# bms_board.net
KiCad netlist of a schematic drawn in EAGLE
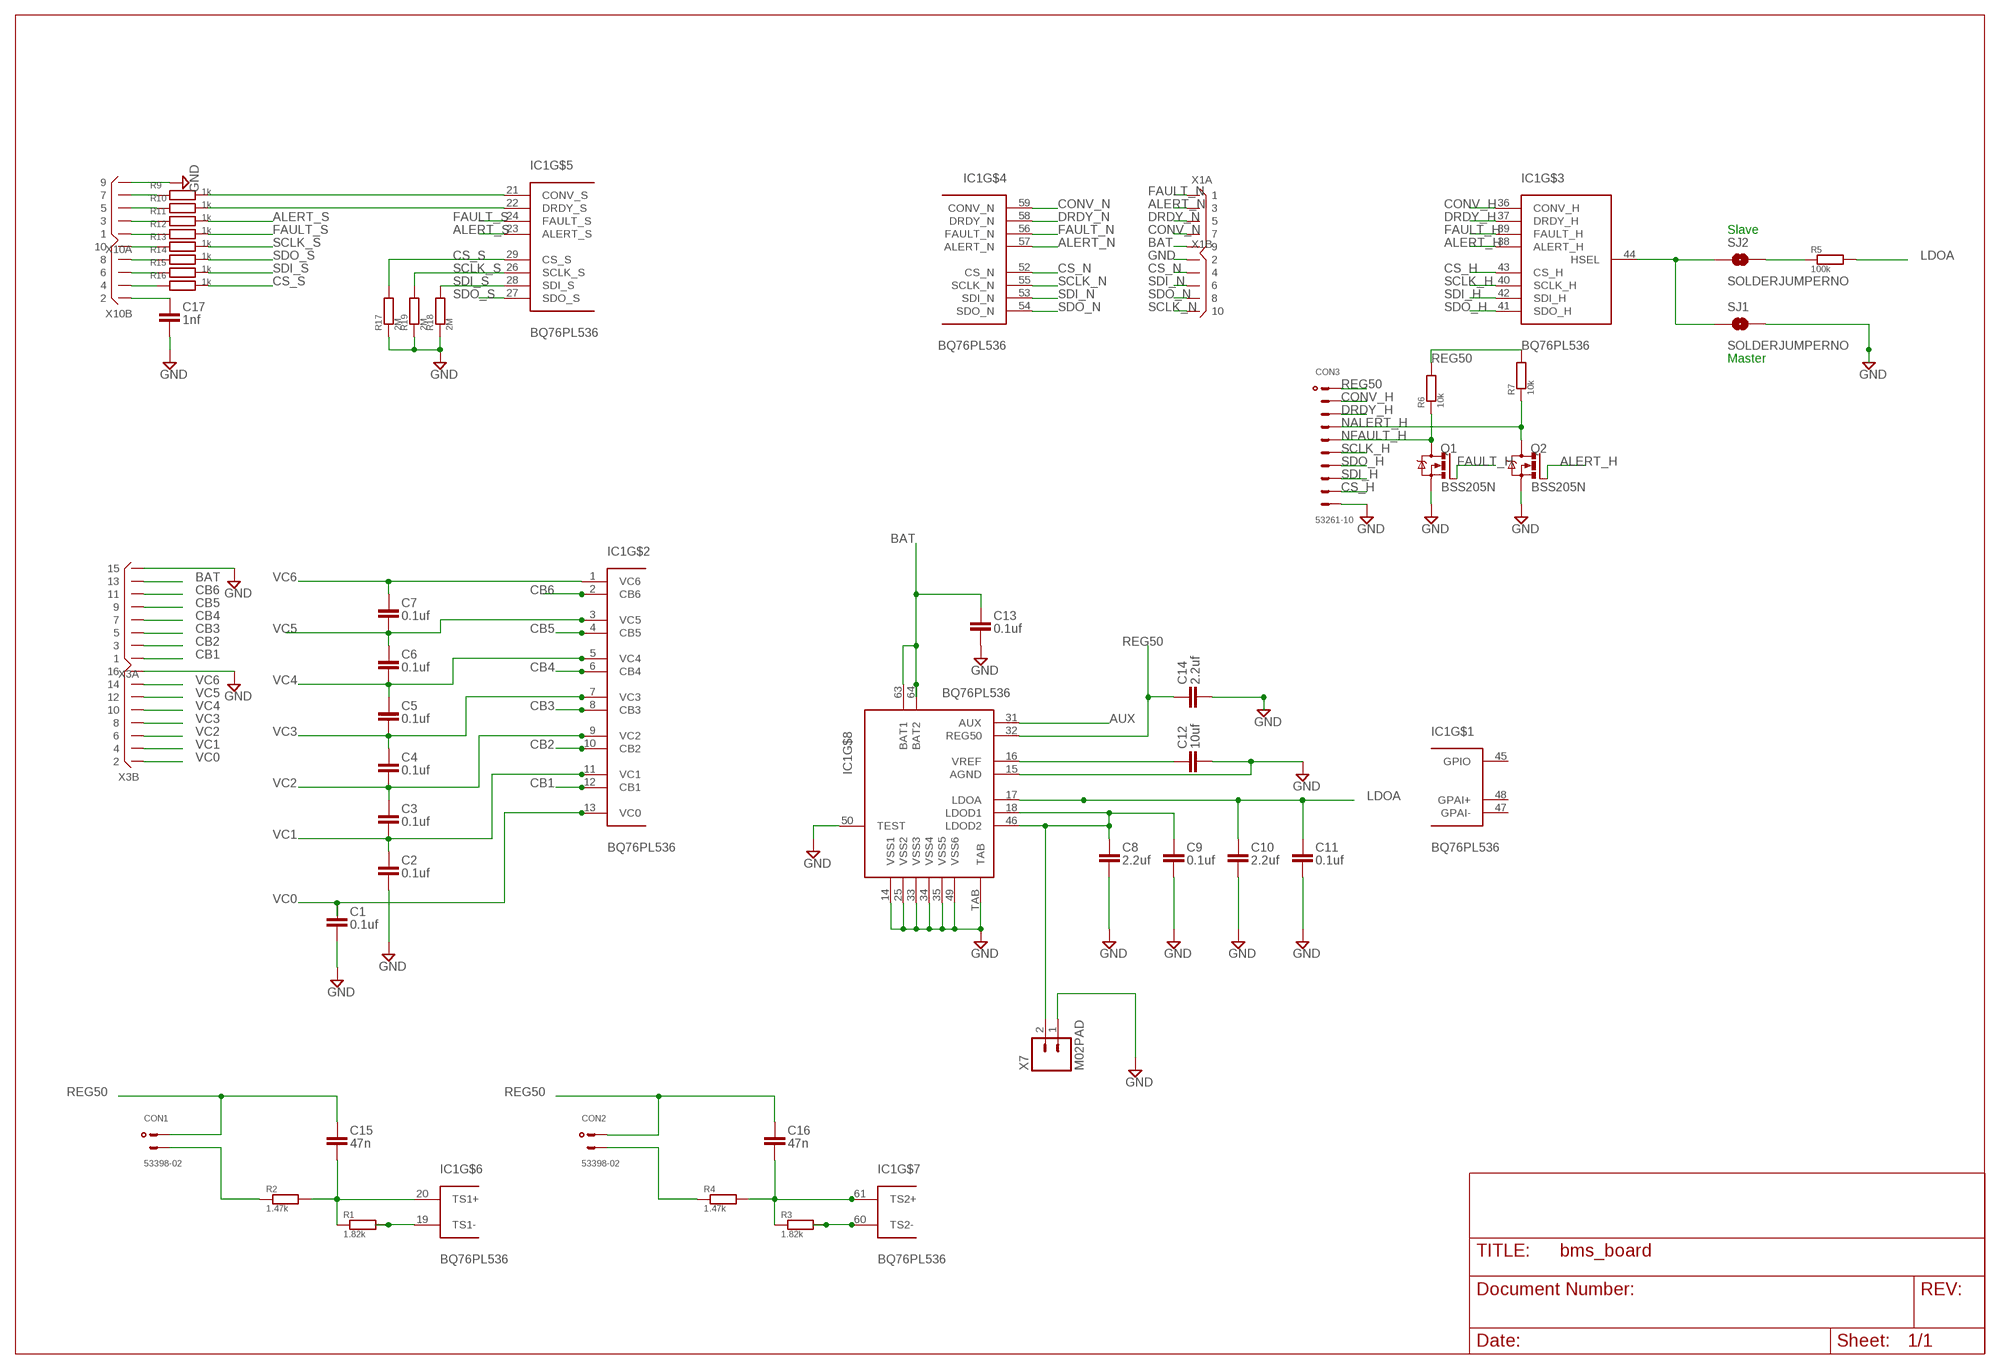
[diagram p0: schematic, sheet 1]

(export (version "E")
  (design (tool "Eeschema 10.0.6"))
  (components
    (comp (ref "C1")
      (value "0.1uf")
      (footprint "eagle-import:C0805")
      (libsource (lib "eagle-import") (part "CSTD"))
    )
    (comp (ref "C2")
      (value "0.1uf")
      (footprint "eagle-import:C0805")
      (libsource (lib "eagle-import") (part "CSTD"))
    )
    (comp (ref "C3")
      (value "0.1uf")
      (footprint "eagle-import:C0805")
      (libsource (lib "eagle-import") (part "CSTD"))
    )
    (comp (ref "C4")
      (value "0.1uf")
      (footprint "eagle-import:C0805")
      (libsource (lib "eagle-import") (part "CSTD"))
    )
    (comp (ref "C5")
      (value "0.1uf")
      (footprint "eagle-import:C0805")
      (libsource (lib "eagle-import") (part "CSTD"))
    )
    (comp (ref "C6")
      (value "0.1uf")
      (footprint "eagle-import:C0805")
      (libsource (lib "eagle-import") (part "CSTD"))
    )
    (comp (ref "C7")
      (value "0.1uf")
      (footprint "eagle-import:C0805")
      (libsource (lib "eagle-import") (part "CSTD"))
    )
    (comp (ref "C8")
      (value "2.2uf")
      (footprint "eagle-import:C0805")
      (libsource (lib "eagle-import") (part "CSTD"))
    )
    (comp (ref "C9")
      (value "0.1uf")
      (footprint "eagle-import:C0805")
      (libsource (lib "eagle-import") (part "CSTD"))
    )
    (comp (ref "C10")
      (value "2.2uf")
      (footprint "eagle-import:C0805")
      (libsource (lib "eagle-import") (part "CSTD"))
    )
    (comp (ref "C11")
      (value "0.1uf")
      (footprint "eagle-import:C0805")
      (libsource (lib "eagle-import") (part "CSTD"))
    )
    (comp (ref "C12")
      (value "10uf")
      (footprint "eagle-import:C0805")
      (libsource (lib "eagle-import") (part "CSTD"))
    )
    (comp (ref "C13")
      (value "0.1uf")
      (footprint "eagle-import:C0805")
      (libsource (lib "eagle-import") (part "CSTD"))
    )
    (comp (ref "C14")
      (value "2.2uf")
      (footprint "eagle-import:C0805")
      (libsource (lib "eagle-import") (part "CSTD"))
    )
    (comp (ref "C15")
      (value "47n")
      (footprint "eagle-import:C0805")
      (libsource (lib "eagle-import") (part "CSTD"))
    )
    (comp (ref "C16")
      (value "47n")
      (footprint "eagle-import:C0805")
      (libsource (lib "eagle-import") (part "CSTD"))
    )
    (comp (ref "C17")
      (value "1nf")
      (footprint "eagle-import:C0805")
      (libsource (lib "eagle-import") (part "CSTD"))
    )
    (comp (ref "CON1")
      (value "53398-02")
      (footprint "eagle-import:53398-02")
      (libsource (lib "eagle-import") (part "53?-02398"))
    )
    (comp (ref "CON2")
      (value "53398-02")
      (footprint "eagle-import:53398-02")
      (libsource (lib "eagle-import") (part "53?-02398"))
    )
    (comp (ref "CON3")
      (value "53261-10")
      (footprint "eagle-import:53261-10")
      (libsource (lib "eagle-import") (part "53?-10261"))
    )
    (comp (ref "IC1")
      (value "BQ76PL536")
      (footprint "eagle-import:LQFP-64")
      (libsource (lib "eagle-import") (part "BQ76PL536"))
    )
    (comp (ref "Q1")
      (value "BSS205N")
      (footprint "eagle-import:SOT23")
      (libsource (lib "eagle-import") (part "BSS205N"))
    )
    (comp (ref "Q2")
      (value "BSS205N")
      (footprint "eagle-import:SOT23")
      (libsource (lib "eagle-import") (part "BSS205N"))
    )
    (comp (ref "R1")
      (value "1.82k")
      (footprint "eagle-import:R0805")
      (libsource (lib "eagle-import") (part "R"))
    )
    (comp (ref "R2")
      (value "1.47k")
      (footprint "eagle-import:R0805")
      (libsource (lib "eagle-import") (part "R"))
    )
    (comp (ref "R3")
      (value "1.82k")
      (footprint "eagle-import:R0805")
      (libsource (lib "eagle-import") (part "R"))
    )
    (comp (ref "R4")
      (value "1.47k")
      (footprint "eagle-import:R0805")
      (libsource (lib "eagle-import") (part "R"))
    )
    (comp (ref "R5")
      (value "100k")
      (footprint "eagle-import:R0805")
      (libsource (lib "eagle-import") (part "R"))
    )
    (comp (ref "R6")
      (value "10k")
      (footprint "eagle-import:R0805")
      (libsource (lib "eagle-import") (part "R"))
    )
    (comp (ref "R7")
      (value "10k")
      (footprint "eagle-import:R0805")
      (libsource (lib "eagle-import") (part "R"))
    )
    (comp (ref "R9")
      (value "1k")
      (footprint "eagle-import:R0805")
      (libsource (lib "eagle-import") (part "R"))
    )
    (comp (ref "R10")
      (value "1k")
      (footprint "eagle-import:R0805")
      (libsource (lib "eagle-import") (part "R"))
    )
    (comp (ref "R11")
      (value "1k")
      (footprint "eagle-import:R0805")
      (libsource (lib "eagle-import") (part "R"))
    )
    (comp (ref "R12")
      (value "1k")
      (footprint "eagle-import:R0805")
      (libsource (lib "eagle-import") (part "R"))
    )
    (comp (ref "R13")
      (value "1k")
      (footprint "eagle-import:R0805")
      (libsource (lib "eagle-import") (part "R"))
    )
    (comp (ref "R14")
      (value "1k")
      (footprint "eagle-import:R0805")
      (libsource (lib "eagle-import") (part "R"))
    )
    (comp (ref "R15")
      (value "1k")
      (footprint "eagle-import:R0805")
      (libsource (lib "eagle-import") (part "R"))
    )
    (comp (ref "R16")
      (value "1k")
      (footprint "eagle-import:R0805")
      (libsource (lib "eagle-import") (part "R"))
    )
    (comp (ref "R17")
      (value "2M")
      (footprint "eagle-import:R0805")
      (libsource (lib "eagle-import") (part "R"))
    )
    (comp (ref "R18")
      (value "2M")
      (footprint "eagle-import:R0805")
      (libsource (lib "eagle-import") (part "R"))
    )
    (comp (ref "R19")
      (value "2M")
      (footprint "eagle-import:R0805")
      (libsource (lib "eagle-import") (part "R"))
    )
    (comp (ref "SJ1")
      (value "SOLDERJUMPERNO")
      (footprint "eagle-import:SJ_2S-NO")
      (libsource (lib "eagle-import") (part "SOLDERJUMPERNO"))
    )
    (comp (ref "SJ2")
      (value "SOLDERJUMPERNO")
      (footprint "eagle-import:SJ_2S-NO")
      (libsource (lib "eagle-import") (part "SOLDERJUMPERNO"))
    )
    (comp (ref "X1")
      (value "X05X2ICR")
      (footprint "eagle-import:X10ICR")
      (libsource (lib "eagle-import") (part "X05X2ICR"))
    )
    (comp (ref "X3")
      (value "X08X2DR")
      (footprint "eagle-import:X16R-DIL")
      (libsource (lib "eagle-import") (part "X08X2DR"))
    )
    (comp (ref "X7")
      (value "M02PAD")
      (footprint "eagle-import:1X02")
      (libsource (lib "eagle-import") (part "M02PAD"))
    )
    (comp (ref "X10")
      (value "X05X2ICR")
      (footprint "eagle-import:X10ICR")
      (libsource (lib "eagle-import") (part "X05X2ICR"))
    )
  )
  (nets
    (net (code "1") (name "/ALERT_H") (class "Default")
      (node (ref "IC1") (pin "38") (pinfunction "ALERT_H_38") (pintype "bidirectional"))
      (node (ref "Q2") (pin "1") (pinfunction "G_1") (pintype "passive"))
    )
    (net (code "2") (name "/ALERT_N") (class "Default")
      (node (ref "IC1") (pin "57") (pinfunction "ALERT_N_57") (pintype "bidirectional"))
      (node (ref "X1") (pin "3") (pinfunction "3_3") (pintype "bidirectional"))
    )
    (net (code "3") (name "/ALERT_S") (class "Default")
      (node (ref "IC1") (pin "23") (pinfunction "ALERT_S_23") (pintype "bidirectional"))
      (node (ref "R11") (pin "2") (pinfunction "2_2") (pintype "passive"))
    )
    (net (code "4") (name "/AUX") (class "Default")
      (node (ref "IC1") (pin "31") (pinfunction "AUX_31") (pintype "bidirectional"))
    )
    (net (code "5") (name "/BAT") (class "Default")
      (node (ref "C13") (pin "2") (pinfunction "2_2") (pintype "passive"))
      (node (ref "IC1") (pin "63") (pinfunction "BAT1_63") (pintype "bidirectional"))
      (node (ref "IC1") (pin "64") (pinfunction "BAT2_64") (pintype "bidirectional"))
      (node (ref "X1") (pin "9") (pinfunction "9_9") (pintype "bidirectional"))
      (node (ref "X3") (pin "13") (pinfunction "13_13") (pintype "bidirectional"))
    )
    (net (code "6") (name "/CB1") (class "Default")
      (node (ref "IC1") (pin "12") (pinfunction "CB1_12") (pintype "bidirectional"))
      (node (ref "X3") (pin "1") (pinfunction "1_1") (pintype "bidirectional"))
    )
    (net (code "7") (name "/CB2") (class "Default")
      (node (ref "IC1") (pin "10") (pinfunction "CB2_10") (pintype "bidirectional"))
      (node (ref "X3") (pin "3") (pinfunction "3_3") (pintype "bidirectional"))
    )
    (net (code "8") (name "/CB3") (class "Default")
      (node (ref "IC1") (pin "8") (pinfunction "CB3_8") (pintype "bidirectional"))
      (node (ref "X3") (pin "5") (pinfunction "5_5") (pintype "bidirectional"))
    )
    (net (code "9") (name "/CB4") (class "Default")
      (node (ref "IC1") (pin "6") (pinfunction "CB4_6") (pintype "bidirectional"))
      (node (ref "X3") (pin "7") (pinfunction "7_7") (pintype "bidirectional"))
    )
    (net (code "10") (name "/CB5") (class "Default")
      (node (ref "IC1") (pin "4") (pinfunction "CB5_4") (pintype "bidirectional"))
      (node (ref "X3") (pin "9") (pinfunction "9_9") (pintype "bidirectional"))
    )
    (net (code "11") (name "/CB6") (class "Default")
      (node (ref "IC1") (pin "2") (pinfunction "CB6_2") (pintype "bidirectional"))
      (node (ref "X3") (pin "11") (pinfunction "11_11") (pintype "bidirectional"))
    )
    (net (code "12") (name "/CONV_H") (class "Default")
      (node (ref "CON3") (pin "2") (pinfunction "2_2") (pintype "passive"))
      (node (ref "IC1") (pin "36") (pinfunction "CONV_H_36") (pintype "bidirectional"))
    )
    (net (code "13") (name "/CONV_N") (class "Default")
      (node (ref "IC1") (pin "59") (pinfunction "CONV_N_59") (pintype "bidirectional"))
      (node (ref "X1") (pin "7") (pinfunction "7_7") (pintype "bidirectional"))
    )
    (net (code "14") (name "/CS_H") (class "Default")
      (node (ref "CON3") (pin "9") (pinfunction "9_9") (pintype "passive"))
      (node (ref "IC1") (pin "43") (pinfunction "CS_H_43") (pintype "bidirectional"))
    )
    (net (code "15") (name "/CS_N") (class "Default")
      (node (ref "IC1") (pin "52") (pinfunction "CS_N_52") (pintype "bidirectional"))
      (node (ref "X1") (pin "4") (pinfunction "4_4") (pintype "bidirectional"))
    )
    (net (code "16") (name "/CS_S") (class "Default")
      (node (ref "IC1") (pin "29") (pinfunction "CS_S_29") (pintype "bidirectional"))
      (node (ref "R16") (pin "2") (pinfunction "2_2") (pintype "passive"))
      (node (ref "R17") (pin "2") (pinfunction "2_2") (pintype "passive"))
    )
    (net (code "17") (name "/DRDY_H") (class "Default")
      (node (ref "CON3") (pin "3") (pinfunction "3_3") (pintype "passive"))
      (node (ref "IC1") (pin "37") (pinfunction "DRDY_H_37") (pintype "bidirectional"))
    )
    (net (code "18") (name "/DRDY_N") (class "Default")
      (node (ref "IC1") (pin "58") (pinfunction "DRDY_N_58") (pintype "bidirectional"))
      (node (ref "X1") (pin "5") (pinfunction "5_5") (pintype "bidirectional"))
    )
    (net (code "19") (name "/FAULT_H") (class "Default")
      (node (ref "IC1") (pin "39") (pinfunction "FAULT_H_39") (pintype "bidirectional"))
      (node (ref "Q1") (pin "1") (pinfunction "G_1") (pintype "passive"))
    )
    (net (code "20") (name "/FAULT_N") (class "Default")
      (node (ref "IC1") (pin "56") (pinfunction "FAULT_N_56") (pintype "bidirectional"))
      (node (ref "X1") (pin "1") (pinfunction "1_1") (pintype "bidirectional"))
    )
    (net (code "21") (name "/FAULT_S") (class "Default")
      (node (ref "IC1") (pin "24") (pinfunction "FAULT_S_24") (pintype "bidirectional"))
      (node (ref "R12") (pin "2") (pinfunction "2_2") (pintype "passive"))
    )
    (net (code "22") (name "/LDOA") (class "Default")
      (node (ref "C10") (pin "2") (pinfunction "2_2") (pintype "passive"))
      (node (ref "C11") (pin "2") (pinfunction "2_2") (pintype "passive"))
      (node (ref "IC1") (pin "17") (pinfunction "LDOA_17") (pintype "bidirectional"))
      (node (ref "R5") (pin "2") (pinfunction "2_2") (pintype "passive"))
    )
    (net (code "23") (name "/NALERT_H") (class "Default")
      (node (ref "CON3") (pin "4") (pinfunction "4_4") (pintype "passive"))
      (node (ref "Q2") (pin "3") (pinfunction "D_3") (pintype "passive"))
      (node (ref "R7") (pin "1") (pinfunction "1_1") (pintype "passive"))
    )
    (net (code "24") (name "/NFAULT_H") (class "Default")
      (node (ref "CON3") (pin "5") (pinfunction "5_5") (pintype "passive"))
      (node (ref "Q1") (pin "3") (pinfunction "D_3") (pintype "passive"))
      (node (ref "R6") (pin "1") (pinfunction "1_1") (pintype "passive"))
    )
    (net (code "25") (name "/REG50") (class "Default")
      (node (ref "C14") (pin "2") (pinfunction "2_2") (pintype "passive"))
      (node (ref "C15") (pin "2") (pinfunction "2_2") (pintype "passive"))
      (node (ref "C16") (pin "2") (pinfunction "2_2") (pintype "passive"))
      (node (ref "CON1") (pin "1") (pinfunction "1_1") (pintype "passive"))
      (node (ref "CON2") (pin "1") (pinfunction "1_1") (pintype "passive"))
      (node (ref "CON3") (pin "1") (pinfunction "1_1") (pintype "passive"))
      (node (ref "IC1") (pin "32") (pinfunction "REG50_32") (pintype "bidirectional"))
      (node (ref "R6") (pin "2") (pinfunction "2_2") (pintype "passive"))
      (node (ref "R7") (pin "2") (pinfunction "2_2") (pintype "passive"))
    )
    (net (code "26") (name "/SCLK_H") (class "Default")
      (node (ref "CON3") (pin "6") (pinfunction "6_6") (pintype "passive"))
      (node (ref "IC1") (pin "40") (pinfunction "SCLK_H_40") (pintype "bidirectional"))
    )
    (net (code "27") (name "/SCLK_N") (class "Default")
      (node (ref "IC1") (pin "55") (pinfunction "SCLK_N_55") (pintype "bidirectional"))
      (node (ref "X1") (pin "10") (pinfunction "10_10") (pintype "bidirectional"))
    )
    (net (code "28") (name "/SCLK_S") (class "Default")
      (node (ref "IC1") (pin "26") (pinfunction "SCLK_S_26") (pintype "bidirectional"))
      (node (ref "R13") (pin "2") (pinfunction "2_2") (pintype "passive"))
      (node (ref "R19") (pin "2") (pinfunction "2_2") (pintype "passive"))
    )
    (net (code "29") (name "/SDI_H") (class "Default")
      (node (ref "CON3") (pin "8") (pinfunction "8_8") (pintype "passive"))
      (node (ref "IC1") (pin "42") (pinfunction "SDI_H_42") (pintype "bidirectional"))
    )
    (net (code "30") (name "/SDI_N") (class "Default")
      (node (ref "IC1") (pin "53") (pinfunction "SDI_N_53") (pintype "bidirectional"))
      (node (ref "X1") (pin "6") (pinfunction "6_6") (pintype "bidirectional"))
    )
    (net (code "31") (name "/SDI_S") (class "Default")
      (node (ref "IC1") (pin "28") (pinfunction "SDI_S_28") (pintype "bidirectional"))
      (node (ref "R15") (pin "2") (pinfunction "2_2") (pintype "passive"))
      (node (ref "R18") (pin "2") (pinfunction "2_2") (pintype "passive"))
    )
    (net (code "32") (name "/SDO_H") (class "Default")
      (node (ref "CON3") (pin "7") (pinfunction "7_7") (pintype "passive"))
      (node (ref "IC1") (pin "41") (pinfunction "SDO_H_41") (pintype "bidirectional"))
    )
    (net (code "33") (name "/SDO_N") (class "Default")
      (node (ref "IC1") (pin "54") (pinfunction "SDO_N_54") (pintype "bidirectional"))
      (node (ref "X1") (pin "8") (pinfunction "8_8") (pintype "bidirectional"))
    )
    (net (code "34") (name "/SDO_S") (class "Default")
      (node (ref "IC1") (pin "27") (pinfunction "SDO_S_27") (pintype "bidirectional"))
      (node (ref "R14") (pin "2") (pinfunction "2_2") (pintype "passive"))
    )
    (net (code "35") (name "/VC0") (class "Default")
      (node (ref "C1") (pin "2") (pinfunction "2_2") (pintype "passive"))
      (node (ref "IC1") (pin "13") (pinfunction "VC0_13") (pintype "bidirectional"))
      (node (ref "X3") (pin "2") (pinfunction "2_2") (pintype "bidirectional"))
    )
    (net (code "36") (name "/VC1") (class "Default")
      (node (ref "C2") (pin "2") (pinfunction "2_2") (pintype "passive"))
      (node (ref "C3") (pin "1") (pinfunction "1_1") (pintype "passive"))
      (node (ref "IC1") (pin "11") (pinfunction "VC1_11") (pintype "bidirectional"))
      (node (ref "X3") (pin "4") (pinfunction "4_4") (pintype "bidirectional"))
    )
    (net (code "37") (name "/VC2") (class "Default")
      (node (ref "C3") (pin "2") (pinfunction "2_2") (pintype "passive"))
      (node (ref "C4") (pin "1") (pinfunction "1_1") (pintype "passive"))
      (node (ref "IC1") (pin "9") (pinfunction "VC2_9") (pintype "bidirectional"))
      (node (ref "X3") (pin "6") (pinfunction "6_6") (pintype "bidirectional"))
    )
    (net (code "38") (name "/VC3") (class "Default")
      (node (ref "C4") (pin "2") (pinfunction "2_2") (pintype "passive"))
      (node (ref "C5") (pin "1") (pinfunction "1_1") (pintype "passive"))
      (node (ref "IC1") (pin "7") (pinfunction "VC3_7") (pintype "bidirectional"))
      (node (ref "X3") (pin "8") (pinfunction "8_8") (pintype "bidirectional"))
    )
    (net (code "39") (name "/VC4") (class "Default")
      (node (ref "C5") (pin "2") (pinfunction "2_2") (pintype "passive"))
      (node (ref "C6") (pin "1") (pinfunction "1_1") (pintype "passive"))
      (node (ref "IC1") (pin "5") (pinfunction "VC4_5") (pintype "bidirectional"))
      (node (ref "X3") (pin "10") (pinfunction "10_10") (pintype "bidirectional"))
    )
    (net (code "40") (name "/VC5") (class "Default")
      (node (ref "C6") (pin "2") (pinfunction "2_2") (pintype "passive"))
      (node (ref "C7") (pin "1") (pinfunction "1_1") (pintype "passive"))
      (node (ref "IC1") (pin "3") (pinfunction "VC5_3") (pintype "bidirectional"))
      (node (ref "X3") (pin "12") (pinfunction "12_12") (pintype "bidirectional"))
    )
    (net (code "41") (name "/VC6") (class "Default")
      (node (ref "C7") (pin "2") (pinfunction "2_2") (pintype "passive"))
      (node (ref "IC1") (pin "1") (pinfunction "VC6_1") (pintype "bidirectional"))
      (node (ref "X3") (pin "14") (pinfunction "14_14") (pintype "bidirectional"))
    )
    (net (code "42") (name "GND") (class "Default")
      (node (ref "C1") (pin "1") (pinfunction "1_1") (pintype "passive"))
      (node (ref "C10") (pin "1") (pinfunction "1_1") (pintype "passive"))
      (node (ref "C11") (pin "1") (pinfunction "1_1") (pintype "passive"))
      (node (ref "C12") (pin "1") (pinfunction "1_1") (pintype "passive"))
      (node (ref "C13") (pin "1") (pinfunction "1_1") (pintype "passive"))
      (node (ref "C14") (pin "1") (pinfunction "1_1") (pintype "passive"))
      (node (ref "C17") (pin "1") (pinfunction "1_1") (pintype "passive"))
      (node (ref "C2") (pin "1") (pinfunction "1_1") (pintype "passive"))
      (node (ref "C8") (pin "1") (pinfunction "1_1") (pintype "passive"))
      (node (ref "C9") (pin "1") (pinfunction "1_1") (pintype "passive"))
      (node (ref "CON3") (pin "10") (pinfunction "10_10") (pintype "passive"))
      (node (ref "IC1") (pin "14") (pinfunction "VSS1_14") (pintype "bidirectional"))
      (node (ref "IC1") (pin "15") (pinfunction "AGND_15") (pintype "bidirectional"))
      (node (ref "IC1") (pin "25") (pinfunction "VSS2_25") (pintype "bidirectional"))
      (node (ref "IC1") (pin "33") (pinfunction "VSS3_33") (pintype "bidirectional"))
      (node (ref "IC1") (pin "34") (pinfunction "VSS4_34") (pintype "bidirectional"))
      (node (ref "IC1") (pin "35") (pinfunction "VSS5_35") (pintype "bidirectional"))
      (node (ref "IC1") (pin "49") (pinfunction "VSS6_49") (pintype "bidirectional"))
      (node (ref "IC1") (pin "50") (pinfunction "TEST_50") (pintype "bidirectional"))
      (node (ref "IC1") (pin "TAB") (pinfunction "TAB_TAB") (pintype "bidirectional"))
      (node (ref "Q1") (pin "2") (pinfunction "S_2") (pintype "passive"))
      (node (ref "Q2") (pin "2") (pinfunction "S_2") (pintype "passive"))
      (node (ref "R17") (pin "1") (pinfunction "1_1") (pintype "passive"))
      (node (ref "R18") (pin "1") (pinfunction "1_1") (pintype "passive"))
      (node (ref "R19") (pin "1") (pinfunction "1_1") (pintype "passive"))
      (node (ref "SJ1") (pin "2") (pinfunction "2_2") (pintype "passive"))
      (node (ref "X1") (pin "2") (pinfunction "2_2") (pintype "bidirectional"))
      (node (ref "X10") (pin "9") (pinfunction "9_9") (pintype "bidirectional"))
      (node (ref "X3") (pin "15") (pinfunction "15_15") (pintype "bidirectional"))
      (node (ref "X3") (pin "16") (pinfunction "16_16") (pintype "bidirectional"))
      (node (ref "X7") (pin "1") (pinfunction "1_1") (pintype "passive"))
    )
    (net (code "43") (name "Net-(C17-Pad2)") (class "Default")
      (node (ref "C17") (pin "2") (pinfunction "2_2") (pintype "passive"))
      (node (ref "X10") (pin "2") (pinfunction "2_2") (pintype "bidirectional"))
    )
    (net (code "44") (name "Net-(CON1-Pad2)") (class "Default")
      (node (ref "CON1") (pin "2") (pinfunction "2_2") (pintype "passive"))
      (node (ref "R2") (pin "1") (pinfunction "1_1") (pintype "passive"))
    )
    (net (code "45") (name "Net-(CON2-Pad2)") (class "Default")
      (node (ref "CON2") (pin "2") (pinfunction "2_2") (pintype "passive"))
      (node (ref "R4") (pin "1") (pinfunction "1_1") (pintype "passive"))
    )
    (net (code "46") (name "Net-(IC1C-HSEL)") (class "Default")
      (node (ref "IC1") (pin "44") (pinfunction "HSEL_44") (pintype "bidirectional"))
      (node (ref "SJ1") (pin "1") (pinfunction "1_1") (pintype "passive"))
      (node (ref "SJ2") (pin "1") (pinfunction "1_1") (pintype "passive"))
    )
    (net (code "47") (name "Net-(IC1E-CONV_S)") (class "Default")
      (node (ref "IC1") (pin "21") (pinfunction "CONV_S_21") (pintype "bidirectional"))
      (node (ref "R9") (pin "2") (pinfunction "2_2") (pintype "passive"))
    )
    (net (code "48") (name "Net-(IC1E-DRDY_S)") (class "Default")
      (node (ref "IC1") (pin "22") (pinfunction "DRDY_S_22") (pintype "bidirectional"))
      (node (ref "R10") (pin "2") (pinfunction "2_2") (pintype "passive"))
    )
    (net (code "49") (name "Net-(IC1F-TS1+)") (class "Default")
      (node (ref "C15") (pin "1") (pinfunction "1_1") (pintype "passive"))
      (node (ref "IC1") (pin "20") (pinfunction "TS1+_20") (pintype "bidirectional"))
      (node (ref "R1") (pin "1") (pinfunction "1_1") (pintype "passive"))
      (node (ref "R2") (pin "2") (pinfunction "2_2") (pintype "passive"))
    )
    (net (code "50") (name "Net-(IC1F-TS1-)") (class "Default")
      (node (ref "IC1") (pin "19") (pinfunction "TS1-_19") (pintype "bidirectional"))
      (node (ref "R1") (pin "2") (pinfunction "2_2") (pintype "passive"))
    )
    (net (code "51") (name "Net-(IC1G-TS2+)") (class "Default")
      (node (ref "C16") (pin "1") (pinfunction "1_1") (pintype "passive"))
      (node (ref "IC1") (pin "61") (pinfunction "TS2+_61") (pintype "bidirectional"))
      (node (ref "R3") (pin "1") (pinfunction "1_1") (pintype "passive"))
      (node (ref "R4") (pin "2") (pinfunction "2_2") (pintype "passive"))
    )
    (net (code "52") (name "Net-(IC1G-TS2-)") (class "Default")
      (node (ref "IC1") (pin "60") (pinfunction "TS2-_60") (pintype "bidirectional"))
      (node (ref "R3") (pin "2") (pinfunction "2_2") (pintype "passive"))
    )
    (net (code "53") (name "Net-(IC1H-LDOD1)") (class "Default")
      (node (ref "C8") (pin "2") (pinfunction "2_2") (pintype "passive"))
      (node (ref "C9") (pin "2") (pinfunction "2_2") (pintype "passive"))
      (node (ref "IC1") (pin "18") (pinfunction "LDOD1_18") (pintype "bidirectional"))
      (node (ref "IC1") (pin "46") (pinfunction "LDOD2_46") (pintype "bidirectional"))
      (node (ref "X7") (pin "2") (pinfunction "2_2") (pintype "passive"))
    )
    (net (code "54") (name "Net-(IC1H-VREF)") (class "Default")
      (node (ref "C12") (pin "2") (pinfunction "2_2") (pintype "passive"))
      (node (ref "IC1") (pin "16") (pinfunction "VREF_16") (pintype "bidirectional"))
    )
    (net (code "55") (name "Net-(R5-Pad1)") (class "Default")
      (node (ref "R5") (pin "1") (pinfunction "1_1") (pintype "passive"))
      (node (ref "SJ2") (pin "2") (pinfunction "2_2") (pintype "passive"))
    )
    (net (code "56") (name "Net-(R9-Pad1)") (class "Default")
      (node (ref "R9") (pin "1") (pinfunction "1_1") (pintype "passive"))
      (node (ref "X10") (pin "7") (pinfunction "7_7") (pintype "bidirectional"))
    )
    (net (code "57") (name "Net-(R10-Pad1)") (class "Default")
      (node (ref "R10") (pin "1") (pinfunction "1_1") (pintype "passive"))
      (node (ref "X10") (pin "5") (pinfunction "5_5") (pintype "bidirectional"))
    )
    (net (code "58") (name "Net-(R11-Pad1)") (class "Default")
      (node (ref "R11") (pin "1") (pinfunction "1_1") (pintype "passive"))
      (node (ref "X10") (pin "3") (pinfunction "3_3") (pintype "bidirectional"))
    )
    (net (code "59") (name "Net-(R12-Pad1)") (class "Default")
      (node (ref "R12") (pin "1") (pinfunction "1_1") (pintype "passive"))
      (node (ref "X10") (pin "1") (pinfunction "1_1") (pintype "bidirectional"))
    )
    (net (code "60") (name "Net-(R13-Pad1)") (class "Default")
      (node (ref "R13") (pin "1") (pinfunction "1_1") (pintype "passive"))
      (node (ref "X10") (pin "10") (pinfunction "10_10") (pintype "bidirectional"))
    )
    (net (code "61") (name "Net-(R14-Pad1)") (class "Default")
      (node (ref "R14") (pin "1") (pinfunction "1_1") (pintype "passive"))
      (node (ref "X10") (pin "8") (pinfunction "8_8") (pintype "bidirectional"))
    )
    (net (code "62") (name "Net-(R15-Pad1)") (class "Default")
      (node (ref "R15") (pin "1") (pinfunction "1_1") (pintype "passive"))
      (node (ref "X10") (pin "6") (pinfunction "6_6") (pintype "bidirectional"))
    )
    (net (code "63") (name "Net-(R16-Pad1)") (class "Default")
      (node (ref "R16") (pin "1") (pinfunction "1_1") (pintype "passive"))
      (node (ref "X10") (pin "4") (pinfunction "4_4") (pintype "bidirectional"))
    )
    (net (code "64") (name "unconnected-(IC1A-GPAI+-Pad48)") (class "Default")
      (node (ref "IC1") (pin "48") (pinfunction "GPAI+_48") (pintype "bidirectional"))
    )
    (net (code "65") (name "unconnected-(IC1A-GPAI--Pad47)") (class "Default")
      (node (ref "IC1") (pin "47") (pinfunction "GPAI-_47") (pintype "bidirectional"))
    )
    (net (code "66") (name "unconnected-(IC1A-GPIO-Pad45)") (class "Default")
      (node (ref "IC1") (pin "45") (pinfunction "GPIO_45") (pintype "bidirectional"))
    )
  )
)
